# power.net
KiCad netlist of a schematic drawn in Altium Designer
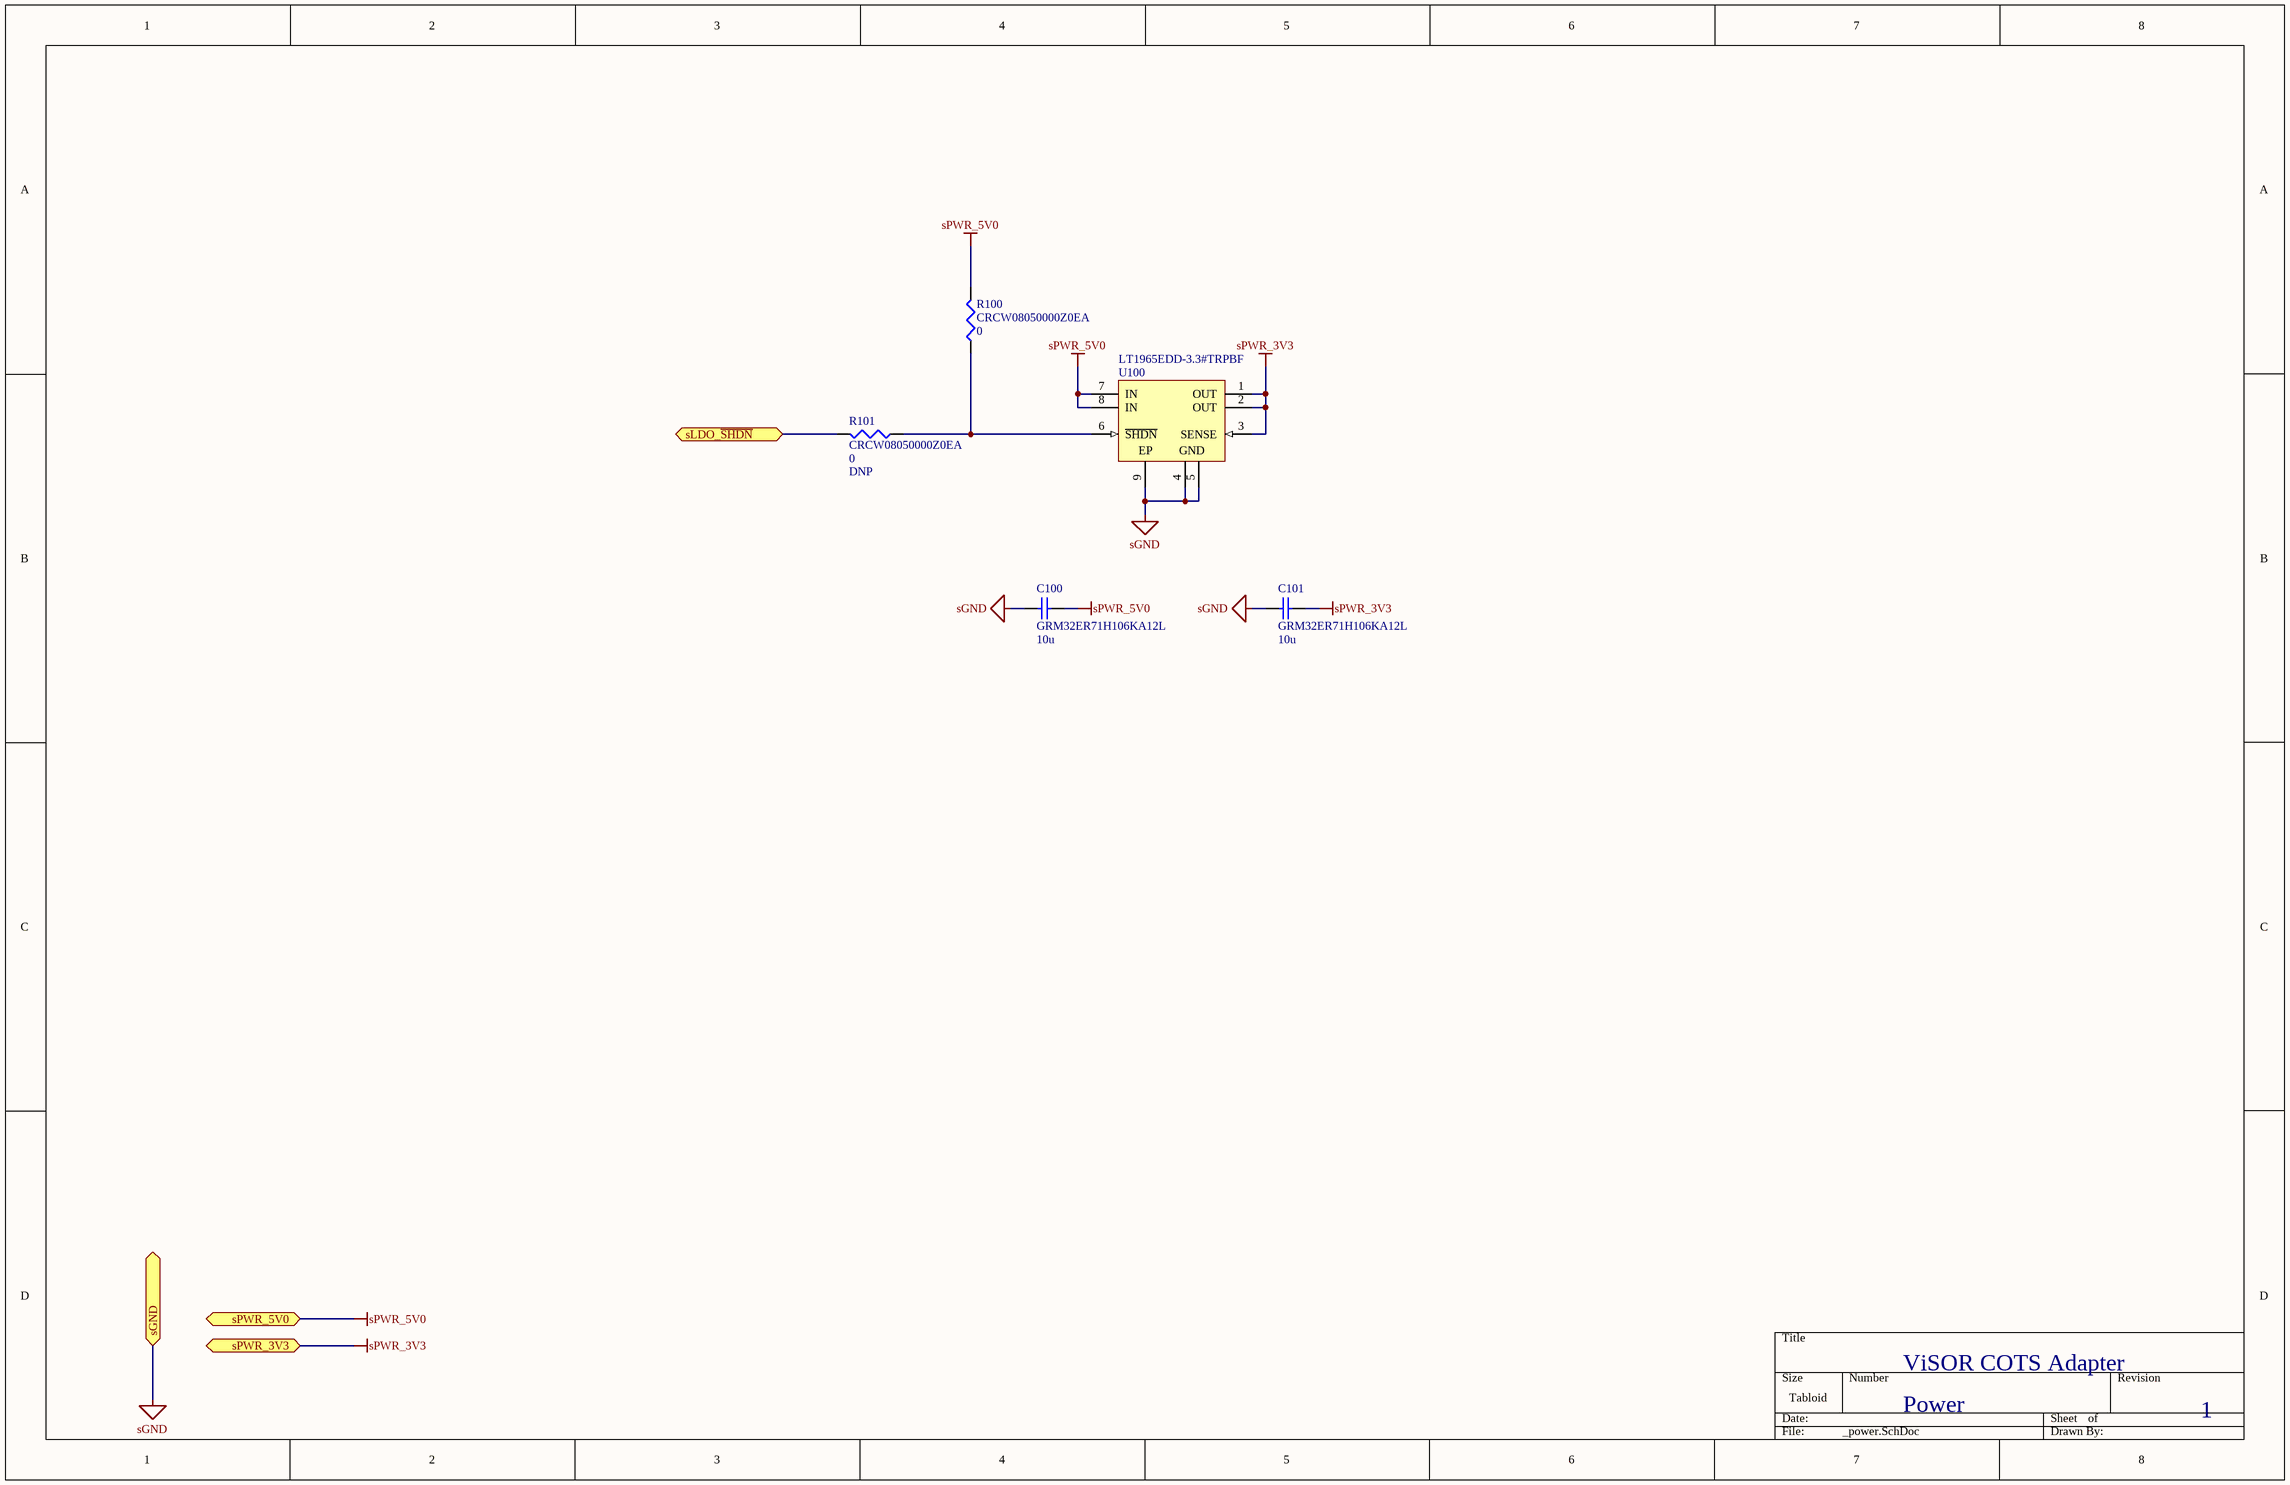
[diagram p0: _power.SchDoc]

(export (version "E")
  (design (tool "Eeschema 10.0.6"))
  (components
    (comp (ref "C100")
      (value "GRM32ER71H106KA12L")
      (footprint "1210")
      (description "-55-125C, 1005, 50V, X7R, ±10%")
      (fields (field (name "ALTIUM_VALUE") "10u"))
      (libsource (lib "standard_capacitors") (part "GRM32ER71HxxxKdddd"))
    )
    (comp (ref "C101")
      (value "GRM32ER71H106KA12L")
      (footprint "1210")
      (description "-55-125C, 1005, 50V, X7R, ±10%")
      (fields (field (name "ALTIUM_VALUE") "10u"))
      (libsource (lib "standard_capacitors") (part "GRM32ER71HxxxKdddd"))
    )
    (comp (ref "R100")
      (value "CRCW08050000Z0EA")
      (footprint "6-0805_M")
      (description "0Ω Resistor")
      (fields (field (name "ALTIUM_VALUE") "0") (field (name "PUBLISHER") "Altium Limited"))
      (libsource (lib "miscellaneous_devices") (part "Res3"))
    )
    (comp (ref "R101")
      (value "CRCW08050000Z0EA")
      (footprint "6-0805_M")
      (description "0Ω Resistor")
      (fields
        (field (name "ALTIUM_VALUE") "0")
        (field (name "ALTIUM_UNNAMED_1") "DNP")
        (field (name "PUBLISHER") "Altium Limited")
      )
      (libsource (lib "miscellaneous_devices") (part "Res3"))
    )
    (comp (ref "U100")
      (value "LT1965EDD-3.3#TRPBF")
      (footprint "LT-DD-8_V - MOD")
      (fields (field (name "MANUFACTURER") "Linear Technology"))
      (libsource (lib "linear_technology") (part "LT1965EDD-3.3#TRPBF"))
    )
  )
  (nets
    (net (code "1") (name "/sLDO_~{SHDN}") (class "Default")
      (node (ref "R101") (pin "2") (pinfunction "2_2") (pintype "passive"))
    )
    (net (code "2") (name "Net-(U100-~{SHDN})") (class "Default")
      (node (ref "R100") (pin "1") (pinfunction "1_1") (pintype "passive"))
      (node (ref "R101") (pin "1") (pinfunction "1_1") (pintype "passive"))
      (node (ref "U100") (pin "6") (pinfunction "~{SHDN}_6") (pintype "input"))
    )
    (net (code "3") (name "sGND") (class "Default")
      (node (ref "C100") (pin "1") (pinfunction "1_1") (pintype "passive"))
      (node (ref "C101") (pin "1") (pinfunction "1_1") (pintype "passive"))
      (node (ref "U100") (pin "4") (pinfunction "GND_4") (pintype "power_in"))
      (node (ref "U100") (pin "5") (pinfunction "GND_5") (pintype "power_in"))
      (node (ref "U100") (pin "9") (pinfunction "EP_9") (pintype "power_in"))
    )
    (net (code "4") (name "sPWR_3V3") (class "Default")
      (node (ref "C101") (pin "2") (pinfunction "2_2") (pintype "passive"))
      (node (ref "U100") (pin "1") (pinfunction "OUT_1") (pintype "power_in"))
      (node (ref "U100") (pin "2") (pinfunction "OUT_2") (pintype "power_in"))
      (node (ref "U100") (pin "3") (pinfunction "SENSE_3") (pintype "input"))
    )
    (net (code "5") (name "sPWR_5V0") (class "Default")
      (node (ref "C100") (pin "2") (pinfunction "2_2") (pintype "passive"))
      (node (ref "R100") (pin "2") (pinfunction "2_2") (pintype "passive"))
      (node (ref "U100") (pin "7") (pinfunction "IN_7") (pintype "power_in"))
      (node (ref "U100") (pin "8") (pinfunction "IN_8") (pintype "power_in"))
    )
  )
)
